# mux.net
KiCad netlist of a schematic drawn in Altium Designer
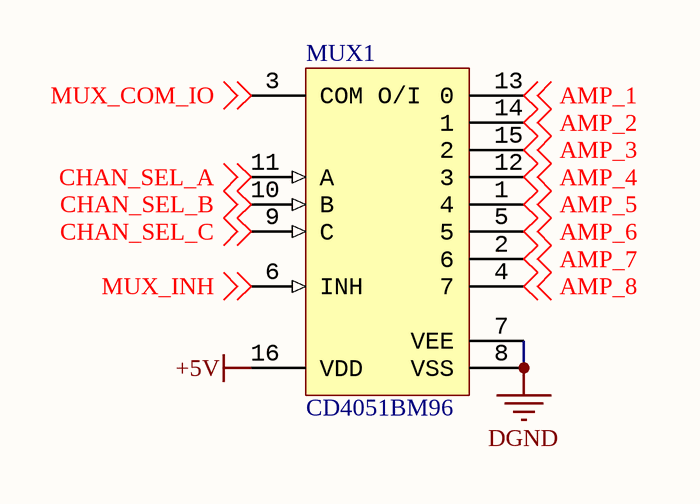
[diagram p0: mux.SchDoc]

(export (version "E")
  (design (tool "Eeschema 10.0.6"))
  (components
    (comp (ref "MUX1")
      (value "CD4051BM96")
      (footprint "D0016A_N")
      (fields
        (field (name "GENERIC PART NUMBER") "CD4051B")
        (field (name "MANUFACTURER") "Texas Instruments")
      )
      (libsource (lib "Altium Content Vault") (part "TI-CD4051B-16"))
    )
  )
  (nets
    (net (code "1") (name "+5V") (class "Default")
      (node (ref "MUX1") (pin "16") (pinfunction "VDD_16") (pintype "power_in"))
    )
    (net (code "2") (name "AMP_1") (class "Default")
      (node (ref "MUX1") (pin "13") (pinfunction "0_13") (pintype "passive"))
    )
    (net (code "3") (name "AMP_2") (class "Default")
      (node (ref "MUX1") (pin "14") (pinfunction "1_14") (pintype "passive"))
    )
    (net (code "4") (name "AMP_3") (class "Default")
      (node (ref "MUX1") (pin "15") (pinfunction "2_15") (pintype "passive"))
    )
    (net (code "5") (name "AMP_4") (class "Default")
      (node (ref "MUX1") (pin "12") (pinfunction "3_12") (pintype "passive"))
    )
    (net (code "6") (name "AMP_5") (class "Default")
      (node (ref "MUX1") (pin "1") (pinfunction "4_1") (pintype "passive"))
    )
    (net (code "7") (name "AMP_6") (class "Default")
      (node (ref "MUX1") (pin "5") (pinfunction "5_5") (pintype "passive"))
    )
    (net (code "8") (name "AMP_7") (class "Default")
      (node (ref "MUX1") (pin "2") (pinfunction "6_2") (pintype "passive"))
    )
    (net (code "9") (name "AMP_8") (class "Default")
      (node (ref "MUX1") (pin "4") (pinfunction "7_4") (pintype "passive"))
    )
    (net (code "10") (name "CHAN_SEL_A") (class "Default")
      (node (ref "MUX1") (pin "11") (pinfunction "A_11") (pintype "input"))
    )
    (net (code "11") (name "CHAN_SEL_B") (class "Default")
      (node (ref "MUX1") (pin "10") (pinfunction "B_10") (pintype "input"))
    )
    (net (code "12") (name "CHAN_SEL_C") (class "Default")
      (node (ref "MUX1") (pin "9") (pinfunction "C_9") (pintype "input"))
    )
    (net (code "13") (name "DGND") (class "Default")
      (node (ref "MUX1") (pin "7") (pinfunction "VEE_7") (pintype "power_in"))
      (node (ref "MUX1") (pin "8") (pinfunction "VSS_8") (pintype "power_in"))
    )
    (net (code "14") (name "MUX_COM_IO") (class "Default")
      (node (ref "MUX1") (pin "3") (pinfunction "COM_O/I_3") (pintype "passive"))
    )
    (net (code "15") (name "MUX_INH") (class "Default")
      (node (ref "MUX1") (pin "6") (pinfunction "INH_6") (pintype "input"))
    )
  )
)
